# M1_Shield_Radio_V1_3_2.net
KiCad netlist of a schematic drawn in EAGLE
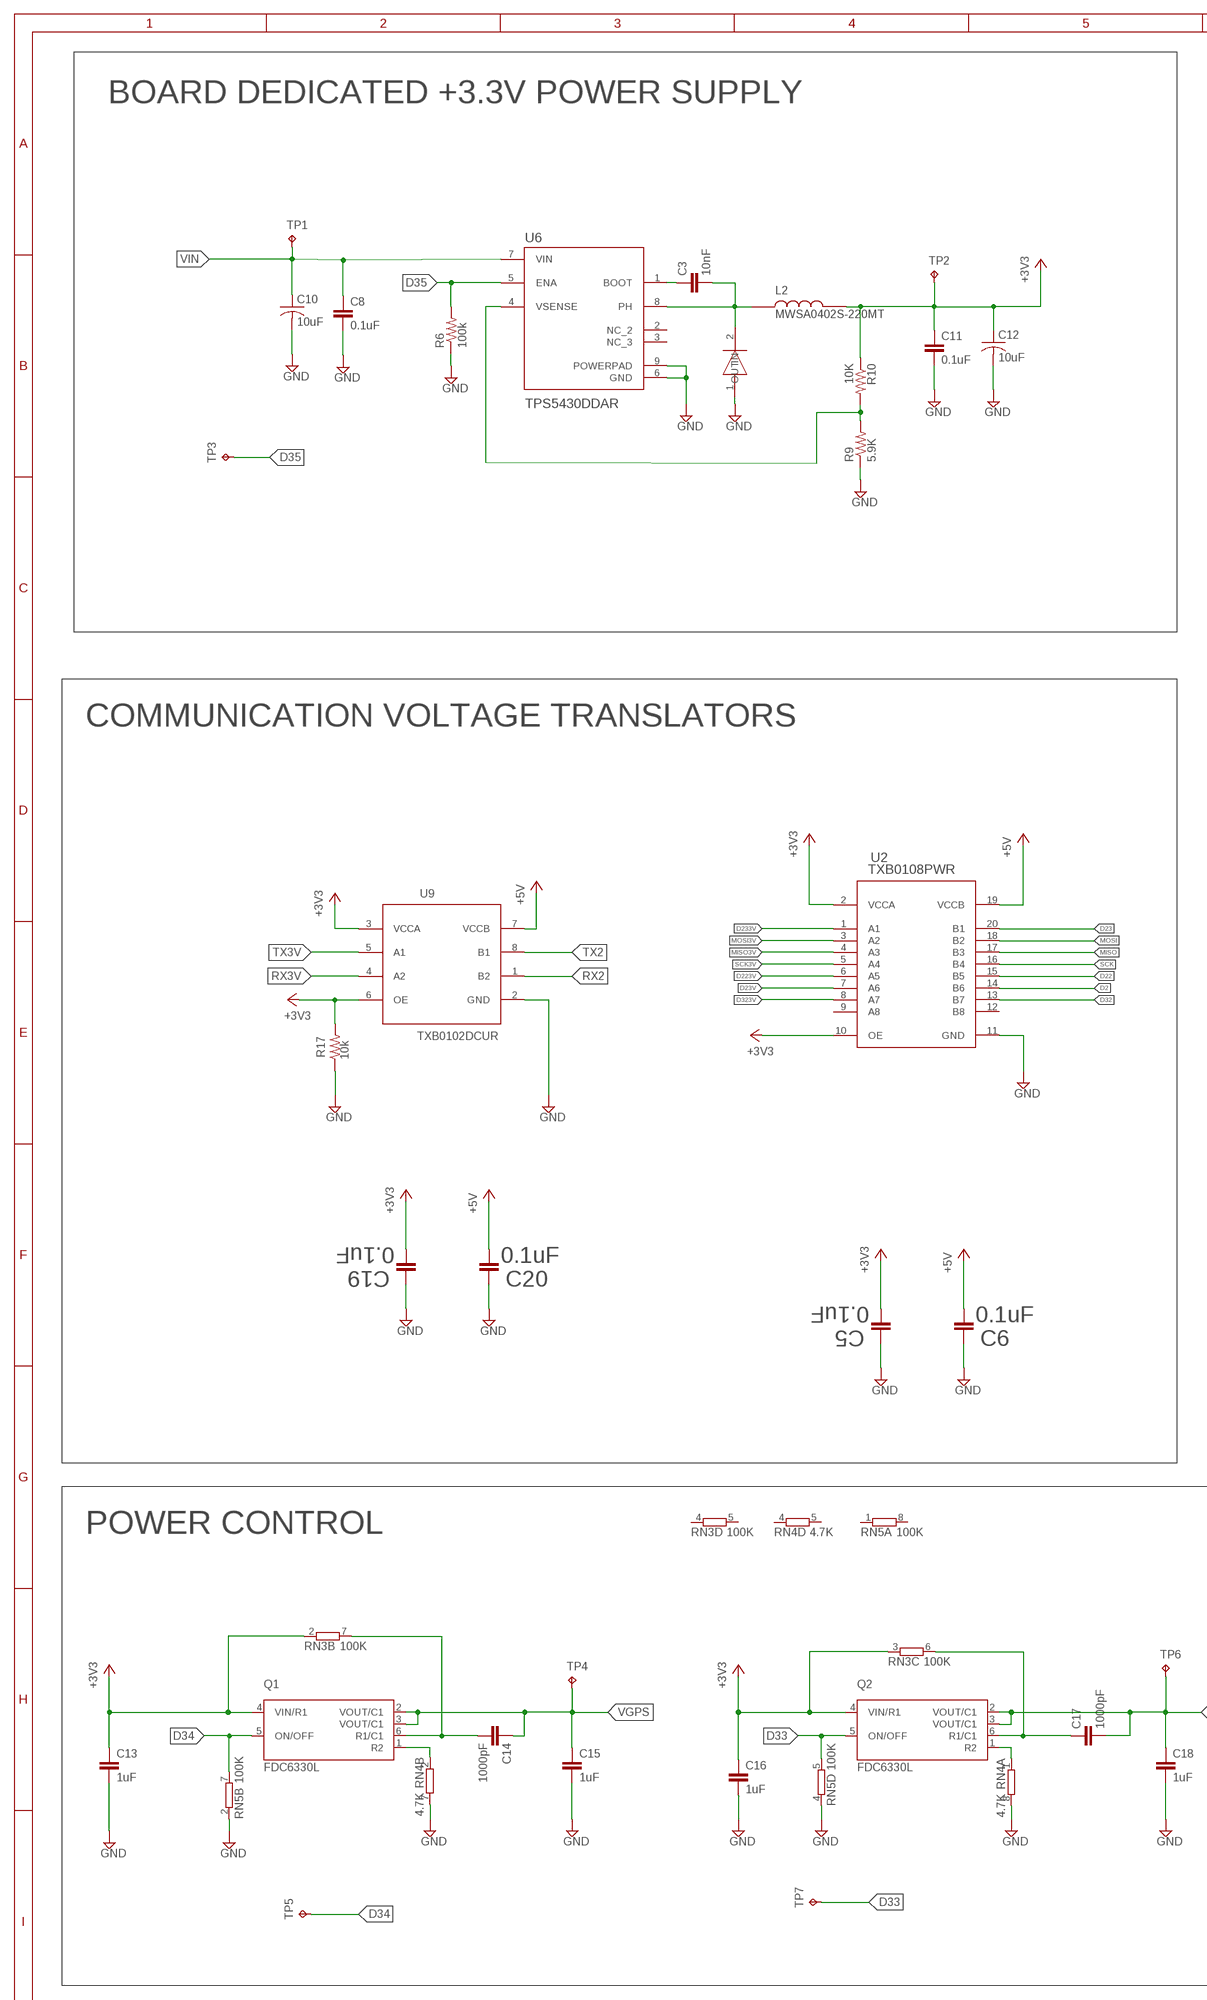
[diagram p0: schematic, sheet 1, part 1 of 2]
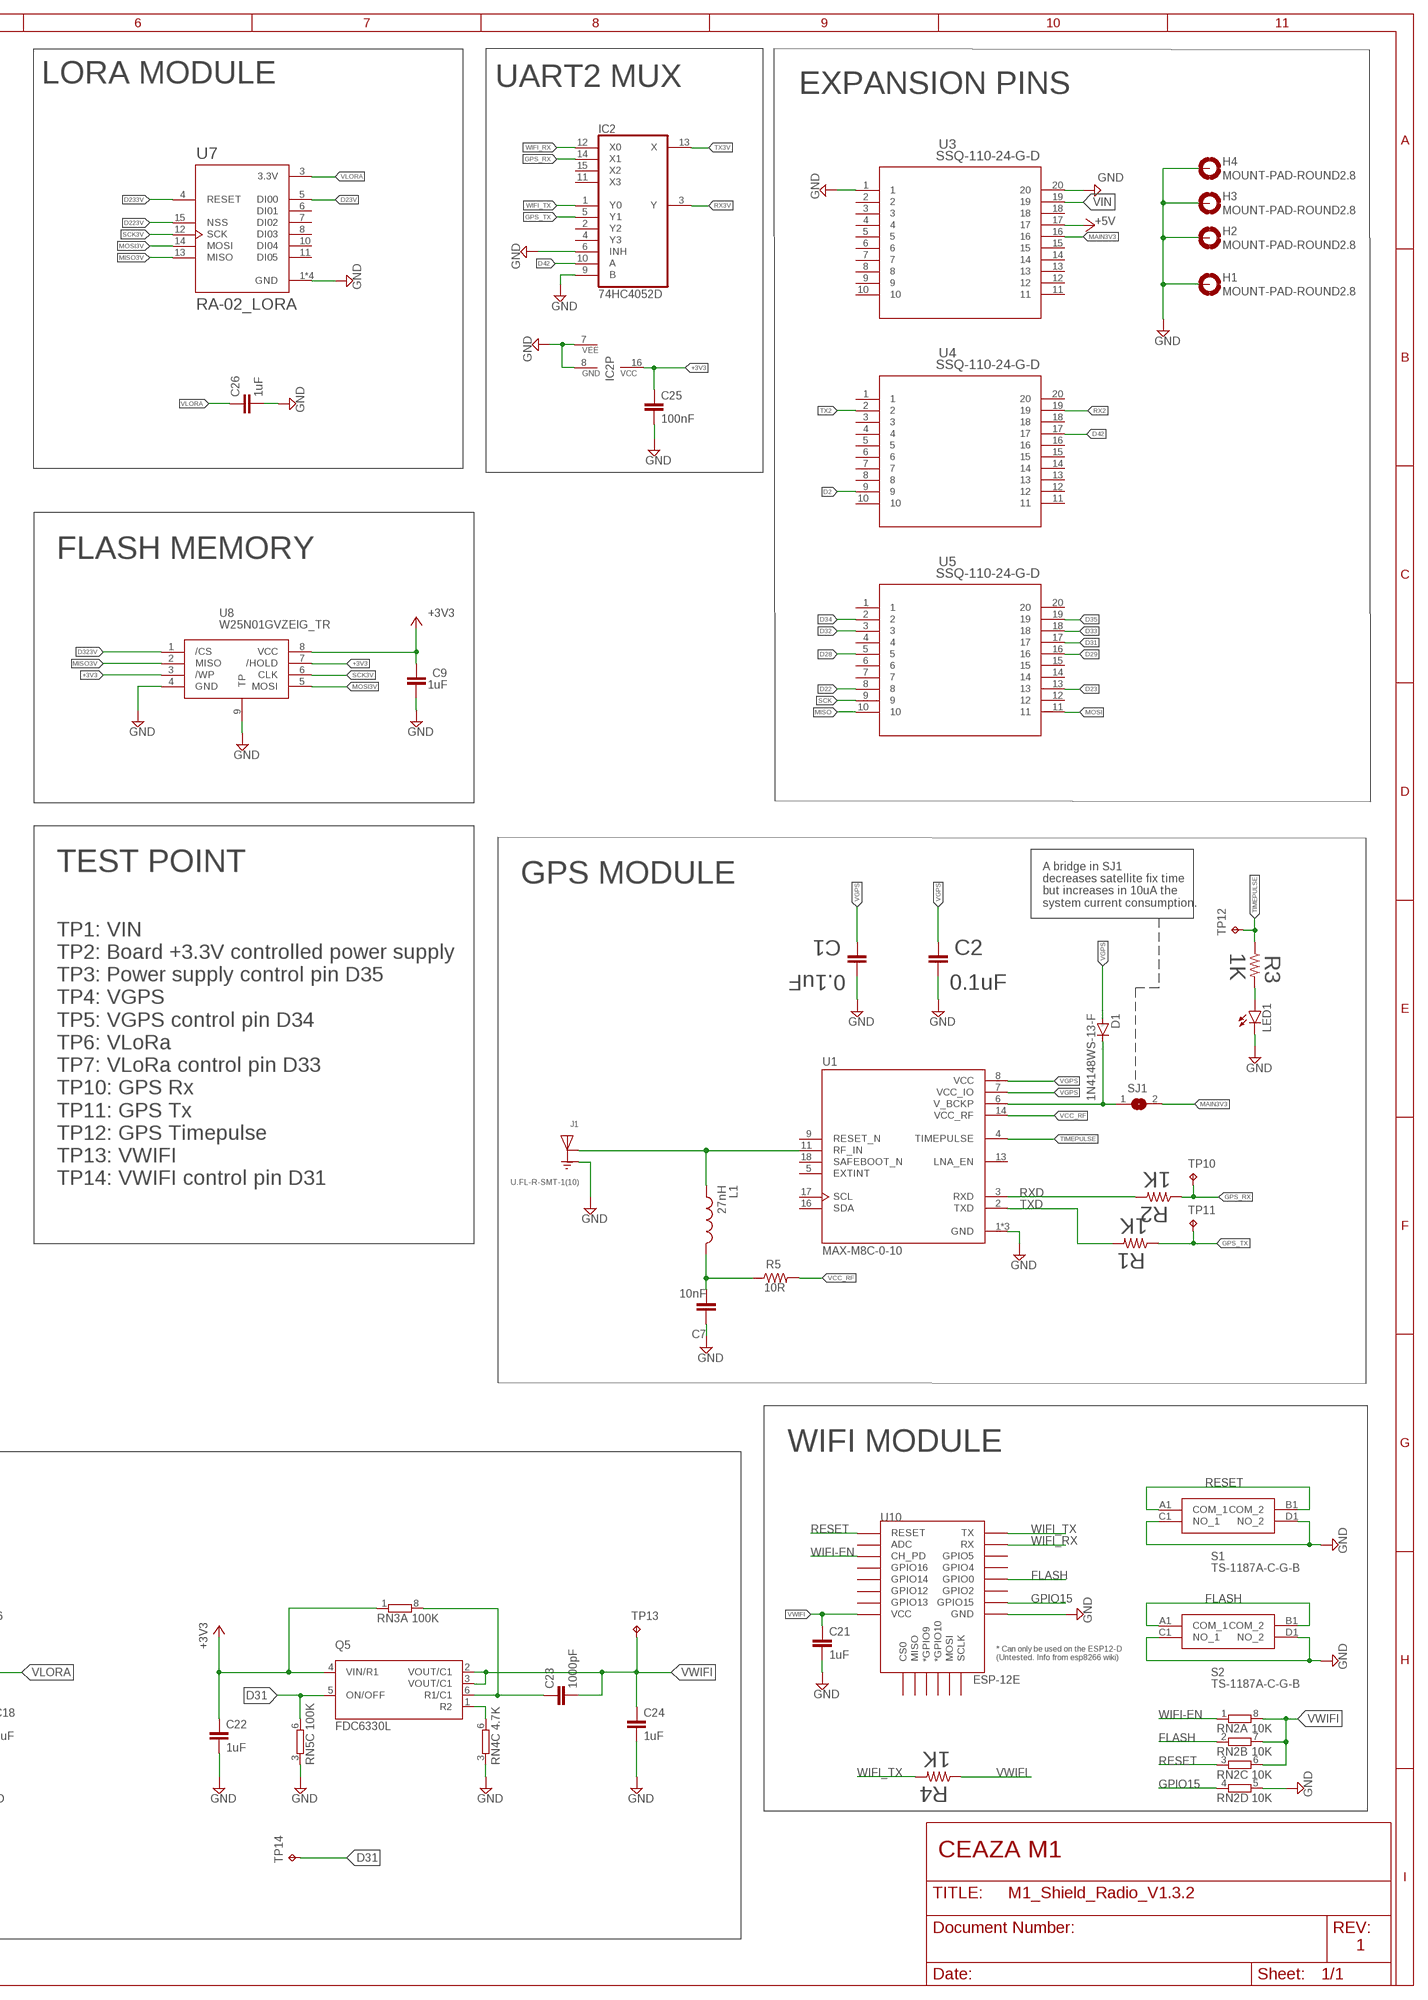
[diagram p1: schematic, sheet 1, part 2 of 2]

(export (version "E")
  (design (tool "Eeschema 10.0.6"))
  (components
    (comp (ref "C1")
      (value "0.1uF")
      (footprint "eagle-import:C0603K")
      (libsource (lib "eagle-import") (part "C-EUC0603K"))
    )
    (comp (ref "C2")
      (value "0.1uF")
      (footprint "eagle-import:C0603K")
      (libsource (lib "eagle-import") (part "C-EUC0603K"))
    )
    (comp (ref "C3")
      (value "10nF")
      (footprint "eagle-import:C0603K")
      (libsource (lib "eagle-import") (part "C-EUC0603K"))
    )
    (comp (ref "C5")
      (value "0.1uF")
      (footprint "eagle-import:C0603K")
      (libsource (lib "eagle-import") (part "C-EUC0603K"))
    )
    (comp (ref "C6")
      (value "0.1uF")
      (footprint "eagle-import:C0603K")
      (libsource (lib "eagle-import") (part "C-EUC0603K"))
    )
    (comp (ref "C7")
      (value "10nF")
      (footprint "eagle-import:C0603K")
      (libsource (lib "eagle-import") (part "C-EUC0603K"))
    )
    (comp (ref "C8")
      (value "0.1uF")
      (footprint "eagle-import:C0603K")
      (libsource (lib "eagle-import") (part "C-EUC0603K"))
    )
    (comp (ref "C9")
      (value "1uF")
      (footprint "eagle-import:C0603K")
      (libsource (lib "eagle-import") (part "C-EUC0603K"))
    )
    (comp (ref "C10")
      (value "10uF")
      (footprint "eagle-import:C0603K")
      (libsource (lib "eagle-import") (part "C-USC0603K"))
    )
    (comp (ref "C11")
      (value "0.1uF")
      (footprint "eagle-import:C0603K")
      (libsource (lib "eagle-import") (part "C-EUC0603K"))
    )
    (comp (ref "C12")
      (value "10uF")
      (footprint "eagle-import:C0603K")
      (libsource (lib "eagle-import") (part "C-USC0603K"))
    )
    (comp (ref "C13")
      (value "1uF")
      (footprint "eagle-import:C0603K")
      (libsource (lib "eagle-import") (part "C-EUC0603K"))
    )
    (comp (ref "C14")
      (value "1000pF")
      (footprint "eagle-import:C0603K")
      (libsource (lib "eagle-import") (part "C-EUC0603K"))
    )
    (comp (ref "C15")
      (value "1uF")
      (footprint "eagle-import:C0603K")
      (libsource (lib "eagle-import") (part "C-EUC0603K"))
    )
    (comp (ref "C16")
      (value "1uF")
      (footprint "eagle-import:C0603K")
      (libsource (lib "eagle-import") (part "C-EUC0603K"))
    )
    (comp (ref "C17")
      (value "1000pF")
      (footprint "eagle-import:C0603K")
      (libsource (lib "eagle-import") (part "C-EUC0603K"))
    )
    (comp (ref "C18")
      (value "1uF")
      (footprint "eagle-import:C0603K")
      (libsource (lib "eagle-import") (part "C-EUC0603K"))
    )
    (comp (ref "C19")
      (value "0.1uF")
      (footprint "eagle-import:C0603K")
      (libsource (lib "eagle-import") (part "C-EUC0603K"))
    )
    (comp (ref "C20")
      (value "0.1uF")
      (footprint "eagle-import:C0603K")
      (libsource (lib "eagle-import") (part "C-EUC0603K"))
    )
    (comp (ref "C21")
      (value "1uF")
      (footprint "eagle-import:C0603K")
      (libsource (lib "eagle-import") (part "C-EUC0603K"))
    )
    (comp (ref "C22")
      (value "1uF")
      (footprint "eagle-import:C0603K")
      (libsource (lib "eagle-import") (part "C-EUC0603K"))
    )
    (comp (ref "C23")
      (value "1000pF")
      (footprint "eagle-import:C0603K")
      (libsource (lib "eagle-import") (part "C-EUC0603K"))
    )
    (comp (ref "C24")
      (value "1uF")
      (footprint "eagle-import:C0603K")
      (libsource (lib "eagle-import") (part "C-EUC0603K"))
    )
    (comp (ref "C25")
      (value "100nF")
      (footprint "eagle-import:C0603K")
      (libsource (lib "eagle-import") (part "C-EUC0603K"))
    )
    (comp (ref "C26")
      (value "1uF")
      (footprint "eagle-import:C0603K")
      (libsource (lib "eagle-import") (part "C-EUC0603K"))
    )
    (comp (ref "D1")
      (value "1N4148WS-13-F")
      (footprint "eagle-import:SOD323-W")
      (libsource (lib "eagle-import") (part "DIODE-SOD323-W"))
    )
    (comp (ref "H1")
      (value "MOUNT-PAD-ROUND2.8")
      (footprint "eagle-import:2,8-PAD")
      (libsource (lib "eagle-import") (part "MOUNT-PAD-ROUND2.8"))
    )
    (comp (ref "H2")
      (value "MOUNT-PAD-ROUND2.8")
      (footprint "eagle-import:2,8-PAD")
      (libsource (lib "eagle-import") (part "MOUNT-PAD-ROUND2.8"))
    )
    (comp (ref "H3")
      (value "MOUNT-PAD-ROUND2.8")
      (footprint "eagle-import:2,8-PAD")
      (libsource (lib "eagle-import") (part "MOUNT-PAD-ROUND2.8"))
    )
    (comp (ref "H4")
      (value "MOUNT-PAD-ROUND2.8")
      (footprint "eagle-import:2,8-PAD")
      (libsource (lib "eagle-import") (part "MOUNT-PAD-ROUND2.8"))
    )
    (comp (ref "IC2")
      (value "74HC4052D")
      (footprint "eagle-import:SO16")
      (libsource (lib "eagle-import") (part "4052D"))
    )
    (comp (ref "J1")
      (value "U.FL-R-SMT-1(10)")
      (footprint "eagle-import:HRS_U.FL-R-SMT-1(10)")
      (fields
        (field (name "DIGI-KEY_PART_NUMBER") "H11891CT-ND")
        (field (name "MF") "Hirose")
        (field (name "MP") "U.FL-R-SMT-1_10_")
      )
      (libsource (lib "eagle-import") (part "U.FL-R-SMT-1(10)"))
    )
    (comp (ref "L1")
      (value "27nH")
      (footprint "eagle-import:INDC1005X55N")
      (fields
        (field (name "DIGI-KEY_PART_NUMBER") "490-2628-1-ND")
        (field (name "MF") "Murata")
        (field (name "MP") "LQG15HS27NJ02D")
      )
      (libsource (lib "eagle-import") (part "LQG15HS27NJ02D"))
    )
    (comp (ref "L2")
      (value "MWSA0402S-220MT")
      (footprint "eagle-import:MWSA0402S-220MT")
      (libsource (lib "eagle-import") (part "MWSA0402S-220MT"))
    )
    (comp (ref "LED1")
      (value "LEDCHIP-LED0805")
      (footprint "eagle-import:CHIP-LED0805")
      (libsource (lib "eagle-import") (part "LEDCHIP-LED0805"))
    )
    (comp (ref "Q1")
      (value "FDC6330L")
      (footprint "eagle-import:SOT95P280X110-6N")
      (fields (field (name "DIGI-KEY_PART_NUMBER") "FDC6330LCT-ND") (field (name "MF") "ON Semiconductor"))
      (libsource (lib "eagle-import") (part "FDC6330L"))
    )
    (comp (ref "Q2")
      (value "FDC6330L")
      (footprint "eagle-import:SOT95P280X110-6N")
      (fields (field (name "DIGI-KEY_PART_NUMBER") "FDC6330LCT-ND") (field (name "MF") "ON Semiconductor"))
      (libsource (lib "eagle-import") (part "FDC6330L"))
    )
    (comp (ref "Q5")
      (value "FDC6330L")
      (footprint "eagle-import:SOT95P280X110-6N")
      (fields (field (name "DIGI-KEY_PART_NUMBER") "FDC6330LCT-ND") (field (name "MF") "ON Semiconductor"))
      (libsource (lib "eagle-import") (part "FDC6330L"))
    )
    (comp (ref "R1")
      (value "1K")
      (footprint "eagle-import:R0603")
      (libsource (lib "eagle-import") (part "R-US_R0603"))
    )
    (comp (ref "R2")
      (value "1K")
      (footprint "eagle-import:R0603")
      (libsource (lib "eagle-import") (part "R-US_R0603"))
    )
    (comp (ref "R3")
      (value "1K")
      (footprint "eagle-import:R0603")
      (libsource (lib "eagle-import") (part "R-US_R0603"))
    )
    (comp (ref "R4")
      (value "1K")
      (footprint "eagle-import:R0603")
      (libsource (lib "eagle-import") (part "R-US_R0603"))
    )
    (comp (ref "R5")
      (value "10R")
      (footprint "eagle-import:R0603")
      (libsource (lib "eagle-import") (part "R-US_R0603"))
    )
    (comp (ref "R6")
      (value "100k")
      (footprint "eagle-import:R0603")
      (libsource (lib "eagle-import") (part "R-US_R0603"))
    )
    (comp (ref "R9")
      (value "5.9K")
      (footprint "eagle-import:R0603")
      (libsource (lib "eagle-import") (part "R-US_R0603"))
    )
    (comp (ref "R10")
      (value "10K")
      (footprint "eagle-import:R0603")
      (libsource (lib "eagle-import") (part "R-US_R0603"))
    )
    (comp (ref "R17")
      (value "10k")
      (footprint "eagle-import:R0603")
      (libsource (lib "eagle-import") (part "R-US_R0603"))
    )
    (comp (ref "RN2")
      (value "10K")
      (footprint "eagle-import:0603-ARV")
      (libsource (lib "eagle-import") (part "4R-N0603-ARV"))
    )
    (comp (ref "RN3")
      (value "100K")
      (footprint "eagle-import:0603-ARV")
      (libsource (lib "eagle-import") (part "4R-N0603-ARV"))
    )
    (comp (ref "RN4")
      (value "4.7K")
      (footprint "eagle-import:0603-ARV")
      (libsource (lib "eagle-import") (part "4R-N0603-ARV"))
    )
    (comp (ref "RN5")
      (value "100K")
      (footprint "eagle-import:0603-ARV")
      (libsource (lib "eagle-import") (part "4R-N0603-ARV"))
    )
    (comp (ref "S1")
      (value "TS-1187A-C-G-B")
      (footprint "eagle-import:TS1187ACGB")
      (libsource (lib "eagle-import") (part "TS-1187A-C-G-B"))
    )
    (comp (ref "S2")
      (value "TS-1187A-C-G-B")
      (footprint "eagle-import:TS1187ACGB")
      (libsource (lib "eagle-import") (part "TS-1187A-C-G-B"))
    )
    (comp (ref "SJ1") (value "SJ") (footprint "eagle-import:SJ") (libsource (lib "eagle-import") (part "SJ")))
    (comp (ref "TP1")
      (value "TPB1,27")
      (footprint "eagle-import:B1,27")
      (libsource (lib "eagle-import") (part "TPB1,27"))
    )
    (comp (ref "TP2")
      (value "TPB1,27")
      (footprint "eagle-import:B1,27")
      (libsource (lib "eagle-import") (part "TPB1,27"))
    )
    (comp (ref "TP3")
      (value "TPB1,27")
      (footprint "eagle-import:B1,27")
      (libsource (lib "eagle-import") (part "TPB1,27"))
    )
    (comp (ref "TP4")
      (value "TPB1,27")
      (footprint "eagle-import:B1,27")
      (libsource (lib "eagle-import") (part "TPB1,27"))
    )
    (comp (ref "TP5")
      (value "TPB1,27")
      (footprint "eagle-import:B1,27")
      (libsource (lib "eagle-import") (part "TPB1,27"))
    )
    (comp (ref "TP6")
      (value "TPB1,27")
      (footprint "eagle-import:B1,27")
      (libsource (lib "eagle-import") (part "TPB1,27"))
    )
    (comp (ref "TP7")
      (value "TPB1,27")
      (footprint "eagle-import:B1,27")
      (libsource (lib "eagle-import") (part "TPB1,27"))
    )
    (comp (ref "TP10")
      (value "TPB1,27")
      (footprint "eagle-import:B1,27")
      (libsource (lib "eagle-import") (part "TPB1,27"))
    )
    (comp (ref "TP11")
      (value "TPB1,27")
      (footprint "eagle-import:B1,27")
      (libsource (lib "eagle-import") (part "TPB1,27"))
    )
    (comp (ref "TP12")
      (value "TPB1,27")
      (footprint "eagle-import:B1,27")
      (libsource (lib "eagle-import") (part "TPB1,27"))
    )
    (comp (ref "TP13")
      (value "TPB1,27")
      (footprint "eagle-import:B1,27")
      (libsource (lib "eagle-import") (part "TPB1,27"))
    )
    (comp (ref "TP14")
      (value "TPB1,27")
      (footprint "eagle-import:B1,27")
      (libsource (lib "eagle-import") (part "TPB1,27"))
    )
    (comp (ref "U$1")
      (value "SMA-SS34")
      (footprint "eagle-import:SMA-SS34")
      (libsource (lib "eagle-import") (part "SMA-SS34"))
    )
    (comp (ref "U1")
      (value "MAX-M8C-0-10")
      (footprint "eagle-import:XCVR_MAX-M8C-0-10")
      (fields (field (name "DIGI-KEY_PART_NUMBER") "672-1002-1-ND") (field (name "MF") "U-Blox America"))
      (libsource (lib "eagle-import") (part "MAX-M8C-0-10"))
    )
    (comp (ref "U2")
      (value "TXB0108PWR")
      (footprint "eagle-import:PW0020A_N")
      (fields (field (name "MANUFACTURER") "Texas Instruments"))
      (libsource (lib "eagle-import") (part "TXB0108PWR"))
    )
    (comp (ref "U3")
      (value "SSQ-110-24-G-D")
      (footprint "eagle-import:1-215307-0")
      (fields (field (name "MANUFACTURER_PART_NUMBER") "1-215307-0"))
      (libsource (lib "eagle-import") (part "1-215307-0"))
    )
    (comp (ref "U4")
      (value "SSQ-110-24-G-D")
      (footprint "eagle-import:1-215307-0")
      (fields (field (name "MANUFACTURER_PART_NUMBER") "1-215307-0"))
      (libsource (lib "eagle-import") (part "1-215307-0"))
    )
    (comp (ref "U5")
      (value "SSQ-110-24-G-D")
      (footprint "eagle-import:1-215307-0")
      (fields (field (name "MANUFACTURER_PART_NUMBER") "1-215307-0"))
      (libsource (lib "eagle-import") (part "1-215307-0"))
    )
    (comp (ref "U6")
      (value "TPS5430DDAR")
      (footprint "eagle-import:CONV_TPS5430DDAR")
      (fields (field (name "MF") "Texas Instruments"))
      (libsource (lib "eagle-import") (part "TPS5430DDAR"))
    )
    (comp (ref "U7")
      (value "RA-02_LORA")
      (footprint "eagle-import:MODULE_RA-02_LORA")
      (fields (field (name "MF") "AI-Thinker") (field (name "MP") "Ra-02 LoRa"))
      (libsource (lib "eagle-import") (part "RA-02_LORA"))
    )
    (comp (ref "U8")
      (value "W25N01GVZEIG_TR")
      (footprint "eagle-import:W25N01GVZEIGTR")
      (libsource (lib "eagle-import") (part "W25N01GVZEIG_TR"))
    )
    (comp (ref "U9")
      (value "TXB0102DCUR")
      (footprint "eagle-import:DCU0008A_L")
      (fields
        (field (name "ALTERNATE_PARTNUMBER") "TXB0102DCUT")
        (field (name "MANUFACTURER") "Texas Instruments")
      )
      (libsource (lib "eagle-import") (part "TXB0102DCURDCU0008A_L"))
    )
    (comp (ref "U10")
      (value "ESP-12E")
      (footprint "eagle-import:ESP12E-SMD")
      (libsource (lib "eagle-import") (part "ESP12ESMD"))
    )
  )
  (nets
    (net (code "1") (name "+3V3") (class "Default")
      (node (ref "C11") (pin "1") (pinfunction "1_1") (pintype "passive"))
      (node (ref "C12") (pin "1") (pinfunction "1_1") (pintype "passive"))
      (node (ref "C13") (pin "1") (pinfunction "1_1") (pintype "passive"))
      (node (ref "C16") (pin "1") (pinfunction "1_1") (pintype "passive"))
      (node (ref "C19") (pin "2") (pinfunction "2_2") (pintype "passive"))
      (node (ref "C22") (pin "1") (pinfunction "1_1") (pintype "passive"))
      (node (ref "C25") (pin "1") (pinfunction "1_1") (pintype "passive"))
      (node (ref "C5") (pin "2") (pinfunction "2_2") (pintype "passive"))
      (node (ref "C9") (pin "1") (pinfunction "1_1") (pintype "passive"))
      (node (ref "IC2") (pin "16") (pinfunction "VCC_16") (pintype "power_in"))
      (node (ref "L2") (pin "P$2") (pinfunction "P$2_P$2") (pintype "bidirectional"))
      (node (ref "Q1") (pin "4") (pinfunction "VIN/R1_4") (pintype "input"))
      (node (ref "Q2") (pin "4") (pinfunction "VIN/R1_4") (pintype "input"))
      (node (ref "Q5") (pin "4") (pinfunction "VIN/R1_4") (pintype "input"))
      (node (ref "R10") (pin "1") (pinfunction "1_1") (pintype "passive"))
      (node (ref "R17") (pin "2") (pinfunction "2_2") (pintype "passive"))
      (node (ref "RN3") (pin "1") (pinfunction "1_1") (pintype "passive"))
      (node (ref "RN3") (pin "2") (pinfunction "1_2") (pintype "passive"))
      (node (ref "RN3") (pin "3") (pinfunction "1_3") (pintype "passive"))
      (node (ref "TP2") (pin "TP") (pinfunction "TP_TP") (pintype "input"))
      (node (ref "U2") (pin "10") (pinfunction "OE_10") (pintype "input"))
      (node (ref "U2") (pin "2") (pinfunction "VCCA_2") (pintype "power_in"))
      (node (ref "U8") (pin "3") (pinfunction "/WP_3") (pintype "bidirectional"))
      (node (ref "U8") (pin "7") (pinfunction "/HOLD_7") (pintype "bidirectional"))
      (node (ref "U8") (pin "8") (pinfunction "VCC_8") (pintype "bidirectional"))
      (node (ref "U9") (pin "3") (pinfunction "VCCA_3") (pintype "power_in"))
      (node (ref "U9") (pin "6") (pinfunction "OE_6") (pintype "input"))
    )
    (net (code "2") (name "+5V") (class "Default")
      (node (ref "C20") (pin "2") (pinfunction "2_2") (pintype "passive"))
      (node (ref "C6") (pin "2") (pinfunction "2_2") (pintype "passive"))
      (node (ref "U2") (pin "19") (pinfunction "VCCB_19") (pintype "power_in"))
      (node (ref "U3") (pin "17") (pinfunction "17_17") (pintype "passive"))
      (node (ref "U9") (pin "7") (pinfunction "VCCB_7") (pintype "power_in"))
    )
    (net (code "3") (name "/FLASH") (class "Default")
      (node (ref "RN2") (pin "2") (pinfunction "1_2") (pintype "passive"))
      (node (ref "S2") (pin "A1") (pinfunction "COM_1_A1") (pintype "bidirectional"))
      (node (ref "S2") (pin "B1") (pinfunction "COM_2_B1") (pintype "bidirectional"))
      (node (ref "U10") (pin "GPIO0") (pinfunction "GPIO0_GPIO0") (pintype "bidirectional"))
    )
    (net (code "4") (name "/GPIO15") (class "Default")
      (node (ref "RN2") (pin "4") (pinfunction "1_4") (pintype "passive"))
      (node (ref "U10") (pin "GPIO15") (pinfunction "GPIO15_GPIO15") (pintype "bidirectional"))
    )
    (net (code "5") (name "/RESET") (class "Default")
      (node (ref "RN2") (pin "3") (pinfunction "1_3") (pintype "passive"))
      (node (ref "S1") (pin "A1") (pinfunction "COM_1_A1") (pintype "bidirectional"))
      (node (ref "S1") (pin "B1") (pinfunction "COM_2_B1") (pintype "bidirectional"))
      (node (ref "U10") (pin "RESET") (pinfunction "RESET_RESET") (pintype "bidirectional"))
    )
    (net (code "6") (name "/RXD") (class "Default")
      (node (ref "R2") (pin "2") (pinfunction "2_2") (pintype "passive"))
      (node (ref "U1") (pin "3") (pinfunction "RXD_3") (pintype "input"))
    )
    (net (code "7") (name "/TXD") (class "Default")
      (node (ref "R1") (pin "2") (pinfunction "2_2") (pintype "passive"))
      (node (ref "U1") (pin "2") (pinfunction "TXD_2") (pintype "output"))
    )
    (net (code "8") (name "/WIFI-EN") (class "Default")
      (node (ref "RN2") (pin "1") (pinfunction "1_1") (pintype "passive"))
      (node (ref "U10") (pin "CH_PD") (pinfunction "CH_PD_CH_PD") (pintype "bidirectional"))
    )
    (net (code "9") (name "D2") (class "Default")
      (node (ref "U2") (pin "14") (pinfunction "B6_14") (pintype "bidirectional"))
      (node (ref "U4") (pin "9") (pinfunction "9_9") (pintype "passive"))
    )
    (net (code "10") (name "D22") (class "Default")
      (node (ref "U2") (pin "15") (pinfunction "B5_15") (pintype "bidirectional"))
      (node (ref "U5") (pin "8") (pinfunction "8_8") (pintype "passive"))
    )
    (net (code "11") (name "D23") (class "Default")
      (node (ref "U2") (pin "20") (pinfunction "B1_20") (pintype "bidirectional"))
      (node (ref "U5") (pin "13") (pinfunction "13_13") (pintype "passive"))
    )
    (net (code "12") (name "D23V") (class "Default")
      (node (ref "U2") (pin "7") (pinfunction "A6_7") (pintype "bidirectional"))
      (node (ref "U7") (pin "5") (pinfunction "DI00_5") (pintype "bidirectional"))
    )
    (net (code "13") (name "D28") (class "Default")
      (node (ref "U5") (pin "5") (pinfunction "5_5") (pintype "passive"))
    )
    (net (code "14") (name "D29") (class "Default")
      (node (ref "U5") (pin "16") (pinfunction "16_16") (pintype "passive"))
    )
    (net (code "15") (name "D31") (class "Default")
      (node (ref "Q5") (pin "5") (pinfunction "ON/OFF_5") (pintype "input"))
      (node (ref "RN5") (pin "6") (pinfunction "2_6") (pintype "passive"))
      (node (ref "TP14") (pin "TP") (pinfunction "TP_TP") (pintype "input"))
      (node (ref "U5") (pin "17") (pinfunction "17_17") (pintype "passive"))
    )
    (net (code "16") (name "D32") (class "Default")
      (node (ref "U2") (pin "13") (pinfunction "B7_13") (pintype "bidirectional"))
      (node (ref "U5") (pin "3") (pinfunction "3_3") (pintype "passive"))
    )
    (net (code "17") (name "D33") (class "Default")
      (node (ref "Q2") (pin "5") (pinfunction "ON/OFF_5") (pintype "input"))
      (node (ref "RN5") (pin "5") (pinfunction "2_5") (pintype "passive"))
      (node (ref "TP7") (pin "TP") (pinfunction "TP_TP") (pintype "input"))
      (node (ref "U5") (pin "18") (pinfunction "18_18") (pintype "passive"))
    )
    (net (code "18") (name "D34") (class "Default")
      (node (ref "Q1") (pin "5") (pinfunction "ON/OFF_5") (pintype "input"))
      (node (ref "RN5") (pin "7") (pinfunction "2_7") (pintype "passive"))
      (node (ref "TP5") (pin "TP") (pinfunction "TP_TP") (pintype "input"))
      (node (ref "U5") (pin "2") (pinfunction "2_2") (pintype "passive"))
    )
    (net (code "19") (name "D35") (class "Default")
      (node (ref "R6") (pin "2") (pinfunction "2_2") (pintype "passive"))
      (node (ref "TP3") (pin "TP") (pinfunction "TP_TP") (pintype "input"))
      (node (ref "U5") (pin "19") (pinfunction "19_19") (pintype "passive"))
      (node (ref "U6") (pin "5") (pinfunction "ENA_5") (pintype "input"))
    )
    (net (code "20") (name "D42") (class "Default")
      (node (ref "IC2") (pin "10") (pinfunction "A_10") (pintype "input"))
      (node (ref "U4") (pin "17") (pinfunction "17_17") (pintype "passive"))
    )
    (net (code "21") (name "D223V") (class "Default")
      (node (ref "U2") (pin "6") (pinfunction "A5_6") (pintype "bidirectional"))
      (node (ref "U7") (pin "15") (pinfunction "NSS_15") (pintype "input"))
    )
    (net (code "22") (name "D233V") (class "Default")
      (node (ref "U2") (pin "1") (pinfunction "A1_1") (pintype "bidirectional"))
      (node (ref "U7") (pin "4") (pinfunction "RESET_4") (pintype "input"))
    )
    (net (code "23") (name "D323V") (class "Default")
      (node (ref "U2") (pin "8") (pinfunction "A7_8") (pintype "bidirectional"))
      (node (ref "U8") (pin "1") (pinfunction "/CS_1") (pintype "bidirectional"))
    )
    (net (code "24") (name "GND") (class "Default")
      (node (ref "C1") (pin "1") (pinfunction "1_1") (pintype "passive"))
      (node (ref "C10") (pin "2") (pinfunction "2_2") (pintype "passive"))
      (node (ref "C11") (pin "2") (pinfunction "2_2") (pintype "passive"))
      (node (ref "C12") (pin "2") (pinfunction "2_2") (pintype "passive"))
      (node (ref "C13") (pin "2") (pinfunction "2_2") (pintype "passive"))
      (node (ref "C15") (pin "2") (pinfunction "2_2") (pintype "passive"))
      (node (ref "C16") (pin "2") (pinfunction "2_2") (pintype "passive"))
      (node (ref "C18") (pin "2") (pinfunction "2_2") (pintype "passive"))
      (node (ref "C19") (pin "1") (pinfunction "1_1") (pintype "passive"))
      (node (ref "C2") (pin "1") (pinfunction "1_1") (pintype "passive"))
      (node (ref "C20") (pin "1") (pinfunction "1_1") (pintype "passive"))
      (node (ref "C21") (pin "2") (pinfunction "2_2") (pintype "passive"))
      (node (ref "C22") (pin "2") (pinfunction "2_2") (pintype "passive"))
      (node (ref "C24") (pin "2") (pinfunction "2_2") (pintype "passive"))
      (node (ref "C25") (pin "2") (pinfunction "2_2") (pintype "passive"))
      (node (ref "C26") (pin "2") (pinfunction "2_2") (pintype "passive"))
      (node (ref "C5") (pin "1") (pinfunction "1_1") (pintype "passive"))
      (node (ref "C6") (pin "1") (pinfunction "1_1") (pintype "passive"))
      (node (ref "C7") (pin "1") (pinfunction "1_1") (pintype "passive"))
      (node (ref "C8") (pin "2") (pinfunction "2_2") (pintype "passive"))
      (node (ref "C9") (pin "2") (pinfunction "2_2") (pintype "passive"))
      (node (ref "H1") (pin "B2,8") (pinfunction "MOUNT_B2,8") (pintype "passive"))
      (node (ref "H2") (pin "B2,8") (pinfunction "MOUNT_B2,8") (pintype "passive"))
      (node (ref "H3") (pin "B2,8") (pinfunction "MOUNT_B2,8") (pintype "passive"))
      (node (ref "H4") (pin "B2,8") (pinfunction "MOUNT_B2,8") (pintype "passive"))
      (node (ref "IC2") (pin "6") (pinfunction "INH_6") (pintype "input"))
      (node (ref "IC2") (pin "7") (pinfunction "VEE_7") (pintype "power_in"))
      (node (ref "IC2") (pin "8") (pinfunction "GND_8") (pintype "power_in"))
      (node (ref "IC2") (pin "9") (pinfunction "B_9") (pintype "input"))
      (node (ref "J1") (pin "1") (pinfunction "GND_1") (pintype "passive"))
      (node (ref "J1") (pin "3") (pinfunction "GND_3") (pintype "passive"))
      (node (ref "LED1") (pin "C") (pinfunction "C_C") (pintype "passive"))
      (node (ref "R17") (pin "1") (pinfunction "1_1") (pintype "passive"))
      (node (ref "R6") (pin "1") (pinfunction "1_1") (pintype "passive"))
      (node (ref "R9") (pin "1") (pinfunction "1_1") (pintype "passive"))
      (node (ref "RN2") (pin "5") (pinfunction "2_5") (pintype "passive"))
      (node (ref "RN4") (pin "3") (pinfunction "1_3") (pintype "passive"))
      (node (ref "RN4") (pin "7") (pinfunction "2_7") (pintype "passive"))
      (node (ref "RN4") (pin "8") (pinfunction "2_8") (pintype "passive"))
      (node (ref "RN5") (pin "2") (pinfunction "1_2") (pintype "passive"))
      (node (ref "RN5") (pin "3") (pinfunction "1_3") (pintype "passive"))
      (node (ref "RN5") (pin "4") (pinfunction "1_4") (pintype "passive"))
      (node (ref "S1") (pin "C1") (pinfunction "NO_1_C1") (pintype "bidirectional"))
      (node (ref "S1") (pin "D1") (pinfunction "NO_2_D1") (pintype "bidirectional"))
      (node (ref "S2") (pin "C1") (pinfunction "NO_1_C1") (pintype "bidirectional"))
      (node (ref "S2") (pin "D1") (pinfunction "NO_2_D1") (pintype "bidirectional"))
      (node (ref "U$1") (pin "1") (pinfunction "IN_1") (pintype "input"))
      (node (ref "U1") (pin "1") (pinfunction "GND_1") (pintype "power_in"))
      (node (ref "U1") (pin "10") (pinfunction "GND_10") (pintype "power_in"))
      (node (ref "U1") (pin "12") (pinfunction "GND_12") (pintype "power_in"))
      (node (ref "U10") (pin "GND") (pinfunction "GND_GND") (pintype "bidirectional"))
      (node (ref "U2") (pin "11") (pinfunction "GND_11") (pintype "power_in"))
      (node (ref "U3") (pin "1") (pinfunction "1_1") (pintype "passive"))
      (node (ref "U3") (pin "20") (pinfunction "20_20") (pintype "passive"))
      (node (ref "U6") (pin "6") (pinfunction "GND_6") (pintype "power_in"))
      (node (ref "U6") (pin "9") (pinfunction "POWERPAD_9") (pintype "power_in"))
      (node (ref "U7") (pin "1") (pinfunction "GND_1") (pintype "power_in"))
      (node (ref "U7") (pin "16") (pinfunction "GND_16") (pintype "power_in"))
      (node (ref "U7") (pin "2") (pinfunction "GND_2") (pintype "power_in"))
      (node (ref "U7") (pin "9") (pinfunction "GND_9") (pintype "power_in"))
      (node (ref "U8") (pin "4") (pinfunction "GND_4") (pintype "bidirectional"))
      (node (ref "U8") (pin "9") (pinfunction "TP_9") (pintype "bidirectional"))
      (node (ref "U9") (pin "2") (pinfunction "GND_2") (pintype "power_in"))
    )
    (net (code "25") (name "GPS_RX") (class "Default")
      (node (ref "IC2") (pin "14") (pinfunction "X1_14") (pintype "bidirectional"))
      (node (ref "R2") (pin "1") (pinfunction "1_1") (pintype "passive"))
      (node (ref "TP10") (pin "TP") (pinfunction "TP_TP") (pintype "input"))
    )
    (net (code "26") (name "GPS_TX") (class "Default")
      (node (ref "IC2") (pin "5") (pinfunction "Y1_5") (pintype "bidirectional"))
      (node (ref "R1") (pin "1") (pinfunction "1_1") (pintype "passive"))
      (node (ref "TP11") (pin "TP") (pinfunction "TP_TP") (pintype "input"))
    )
    (net (code "27") (name "MAIN3V3") (class "Default")
      (node (ref "SJ1") (pin "2") (pinfunction "2_2") (pintype "passive"))
      (node (ref "U3") (pin "16") (pinfunction "16_16") (pintype "passive"))
    )
    (net (code "28") (name "MISO") (class "Default")
      (node (ref "U2") (pin "17") (pinfunction "B3_17") (pintype "bidirectional"))
      (node (ref "U5") (pin "10") (pinfunction "10_10") (pintype "passive"))
    )
    (net (code "29") (name "MISO3V") (class "Default")
      (node (ref "U2") (pin "4") (pinfunction "A3_4") (pintype "bidirectional"))
      (node (ref "U7") (pin "13") (pinfunction "MISO_13") (pintype "output"))
      (node (ref "U8") (pin "2") (pinfunction "MISO_2") (pintype "bidirectional"))
    )
    (net (code "30") (name "MOSI") (class "Default")
      (node (ref "U2") (pin "18") (pinfunction "B2_18") (pintype "bidirectional"))
      (node (ref "U5") (pin "11") (pinfunction "11_11") (pintype "passive"))
    )
    (net (code "31") (name "MOSI3V") (class "Default")
      (node (ref "U2") (pin "3") (pinfunction "A2_3") (pintype "bidirectional"))
      (node (ref "U7") (pin "14") (pinfunction "MOSI_14") (pintype "input"))
      (node (ref "U8") (pin "5") (pinfunction "MOSI_5") (pintype "bidirectional"))
    )
    (net (code "32") (name "Net-(C7-Pad2)") (class "Default")
      (node (ref "C7") (pin "2") (pinfunction "2_2") (pintype "passive"))
      (node (ref "L1") (pin "2") (pinfunction "2_2") (pintype "passive"))
      (node (ref "R5") (pin "1") (pinfunction "1_1") (pintype "passive"))
    )
    (net (code "33") (name "Net-(J1-SIG)") (class "Default")
      (node (ref "J1") (pin "2") (pinfunction "SIG_2") (pintype "passive"))
      (node (ref "L1") (pin "1") (pinfunction "1_1") (pintype "passive"))
      (node (ref "U1") (pin "11") (pinfunction "RF_IN_11") (pintype "input"))
    )
    (net (code "34") (name "Net-(LED1-PadA)") (class "Default")
      (node (ref "LED1") (pin "A") (pinfunction "A_A") (pintype "passive"))
      (node (ref "R3") (pin "2") (pinfunction "2_2") (pintype "passive"))
    )
    (net (code "35") (name "Net-(Q1-R1{slash}C1)") (class "Default")
      (node (ref "C14") (pin "2") (pinfunction "2_2") (pintype "passive"))
      (node (ref "Q1") (pin "6") (pinfunction "R1/C1_6") (pintype "passive"))
      (node (ref "RN3") (pin "7") (pinfunction "2_7") (pintype "passive"))
    )
    (net (code "36") (name "Net-(Q1-R2)") (class "Default")
      (node (ref "Q1") (pin "1") (pinfunction "R2_1") (pintype "passive"))
      (node (ref "RN4") (pin "2") (pinfunction "1_2") (pintype "passive"))
    )
    (net (code "37") (name "Net-(Q2-R1{slash}C1)") (class "Default")
      (node (ref "C17") (pin "1") (pinfunction "1_1") (pintype "passive"))
      (node (ref "Q2") (pin "6") (pinfunction "R1/C1_6") (pintype "passive"))
      (node (ref "RN3") (pin "6") (pinfunction "2_6") (pintype "passive"))
    )
    (net (code "38") (name "Net-(Q2-R2)") (class "Default")
      (node (ref "Q2") (pin "1") (pinfunction "R2_1") (pintype "passive"))
      (node (ref "RN4") (pin "1") (pinfunction "1_1") (pintype "passive"))
    )
    (net (code "39") (name "Net-(Q5-R1{slash}C1)") (class "Default")
      (node (ref "C23") (pin "1") (pinfunction "1_1") (pintype "passive"))
      (node (ref "Q5") (pin "6") (pinfunction "R1/C1_6") (pintype "passive"))
      (node (ref "RN3") (pin "8") (pinfunction "2_8") (pintype "passive"))
    )
    (net (code "40") (name "Net-(Q5-R2)") (class "Default")
      (node (ref "Q5") (pin "1") (pinfunction "R2_1") (pintype "passive"))
      (node (ref "RN4") (pin "6") (pinfunction "2_6") (pintype "passive"))
    )
    (net (code "41") (name "Net-(U$1-OUT)") (class "Default")
      (node (ref "C3") (pin "2") (pinfunction "2_2") (pintype "passive"))
      (node (ref "L2") (pin "P$1") (pinfunction "P$1_P$1") (pintype "bidirectional"))
      (node (ref "U$1") (pin "2") (pinfunction "OUT_2") (pintype "bidirectional"))
      (node (ref "U6") (pin "8") (pinfunction "PH_8") (pintype "bidirectional"))
    )
    (net (code "42") (name "Net-(U1-V_BCKP)") (class "Default")
      (node (ref "D1") (pin "C") (pinfunction "C_C") (pintype "passive"))
      (node (ref "SJ1") (pin "1") (pinfunction "1_1") (pintype "passive"))
      (node (ref "U1") (pin "6") (pinfunction "V_BCKP_6") (pintype "power_in"))
    )
    (net (code "43") (name "Net-(U6-BOOT)") (class "Default")
      (node (ref "C3") (pin "1") (pinfunction "1_1") (pintype "passive"))
      (node (ref "U6") (pin "1") (pinfunction "BOOT_1") (pintype "output"))
    )
    (net (code "44") (name "Net-(U6-VSENSE)") (class "Default")
      (node (ref "R10") (pin "2") (pinfunction "2_2") (pintype "passive"))
      (node (ref "R9") (pin "2") (pinfunction "2_2") (pintype "passive"))
      (node (ref "U6") (pin "4") (pinfunction "VSENSE_4") (pintype "input"))
    )
    (net (code "45") (name "RX2") (class "Default")
      (node (ref "U4") (pin "19") (pinfunction "19_19") (pintype "passive"))
      (node (ref "U9") (pin "1") (pinfunction "B2_1") (pintype "bidirectional"))
    )
    (net (code "46") (name "RX3V") (class "Default")
      (node (ref "IC2") (pin "3") (pinfunction "Y_3") (pintype "bidirectional"))
      (node (ref "U9") (pin "4") (pinfunction "A2_4") (pintype "bidirectional"))
    )
    (net (code "47") (name "SCK") (class "Default")
      (node (ref "U2") (pin "16") (pinfunction "B4_16") (pintype "bidirectional"))
      (node (ref "U5") (pin "9") (pinfunction "9_9") (pintype "passive"))
    )
    (net (code "48") (name "SCK3V") (class "Default")
      (node (ref "U2") (pin "5") (pinfunction "A4_5") (pintype "bidirectional"))
      (node (ref "U7") (pin "12") (pinfunction "SCK_12") (pintype "input"))
      (node (ref "U8") (pin "6") (pinfunction "CLK_6") (pintype "bidirectional"))
    )
    (net (code "49") (name "TIMEPULSE") (class "Default")
      (node (ref "R3") (pin "1") (pinfunction "1_1") (pintype "passive"))
      (node (ref "TP12") (pin "TP") (pinfunction "TP_TP") (pintype "input"))
      (node (ref "U1") (pin "4") (pinfunction "TIMEPULSE_4") (pintype "output"))
    )
    (net (code "50") (name "TX2") (class "Default")
      (node (ref "U4") (pin "2") (pinfunction "2_2") (pintype "passive"))
      (node (ref "U9") (pin "8") (pinfunction "B1_8") (pintype "bidirectional"))
    )
    (net (code "51") (name "TX3V") (class "Default")
      (node (ref "IC2") (pin "13") (pinfunction "X_13") (pintype "bidirectional"))
      (node (ref "U9") (pin "5") (pinfunction "A1_5") (pintype "bidirectional"))
    )
    (net (code "52") (name "VCC_RF") (class "Default")
      (node (ref "R5") (pin "2") (pinfunction "2_2") (pintype "passive"))
      (node (ref "U1") (pin "14") (pinfunction "VCC_RF_14") (pintype "power_in"))
    )
    (net (code "53") (name "VGPS") (class "Default")
      (node (ref "C1") (pin "2") (pinfunction "2_2") (pintype "passive"))
      (node (ref "C14") (pin "1") (pinfunction "1_1") (pintype "passive"))
      (node (ref "C15") (pin "1") (pinfunction "1_1") (pintype "passive"))
      (node (ref "C2") (pin "2") (pinfunction "2_2") (pintype "passive"))
      (node (ref "D1") (pin "A") (pinfunction "A_A") (pintype "passive"))
      (node (ref "Q1") (pin "2") (pinfunction "VOUT/C1_2") (pintype "output"))
      (node (ref "Q1") (pin "3") (pinfunction "VOUT/C1_3") (pintype "output"))
      (node (ref "TP4") (pin "TP") (pinfunction "TP_TP") (pintype "input"))
      (node (ref "U1") (pin "7") (pinfunction "VCC_IO_7") (pintype "power_in"))
      (node (ref "U1") (pin "8") (pinfunction "VCC_8") (pintype "power_in"))
    )
    (net (code "54") (name "VIN") (class "Default")
      (node (ref "C10") (pin "1") (pinfunction "1_1") (pintype "passive"))
      (node (ref "C8") (pin "1") (pinfunction "1_1") (pintype "passive"))
      (node (ref "TP1") (pin "TP") (pinfunction "TP_TP") (pintype "input"))
      (node (ref "U3") (pin "19") (pinfunction "19_19") (pintype "passive"))
      (node (ref "U6") (pin "7") (pinfunction "VIN_7") (pintype "power_in"))
    )
    (net (code "55") (name "VLORA") (class "Default")
      (node (ref "C17") (pin "2") (pinfunction "2_2") (pintype "passive"))
      (node (ref "C18") (pin "1") (pinfunction "1_1") (pintype "passive"))
      (node (ref "C26") (pin "1") (pinfunction "1_1") (pintype "passive"))
      (node (ref "Q2") (pin "2") (pinfunction "VOUT/C1_2") (pintype "output"))
      (node (ref "Q2") (pin "3") (pinfunction "VOUT/C1_3") (pintype "output"))
      (node (ref "TP6") (pin "TP") (pinfunction "TP_TP") (pintype "input"))
      (node (ref "U7") (pin "3") (pinfunction "3.3V_3") (pintype "power_in"))
    )
    (net (code "56") (name "VWIFI") (class "Default")
      (node (ref "C21") (pin "1") (pinfunction "1_1") (pintype "passive"))
      (node (ref "C23") (pin "2") (pinfunction "2_2") (pintype "passive"))
      (node (ref "C24") (pin "1") (pinfunction "1_1") (pintype "passive"))
      (node (ref "Q5") (pin "2") (pinfunction "VOUT/C1_2") (pintype "output"))
      (node (ref "Q5") (pin "3") (pinfunction "VOUT/C1_3") (pintype "output"))
      (node (ref "R4") (pin "1") (pinfunction "1_1") (pintype "passive"))
      (node (ref "RN2") (pin "6") (pinfunction "2_6") (pintype "passive"))
      (node (ref "RN2") (pin "7") (pinfunction "2_7") (pintype "passive"))
      (node (ref "RN2") (pin "8") (pinfunction "2_8") (pintype "passive"))
      (node (ref "TP13") (pin "TP") (pinfunction "TP_TP") (pintype "input"))
      (node (ref "U10") (pin "VCC") (pinfunction "VCC_VCC") (pintype "bidirectional"))
    )
    (net (code "57") (name "WIFI_RX") (class "Default")
      (node (ref "IC2") (pin "12") (pinfunction "X0_12") (pintype "bidirectional"))
      (node (ref "U10") (pin "RXD0") (pinfunction "RX_RXD0") (pintype "bidirectional"))
    )
    (net (code "58") (name "WIFI_TX") (class "Default")
      (node (ref "IC2") (pin "1") (pinfunction "Y0_1") (pintype "bidirectional"))
      (node (ref "R4") (pin "2") (pinfunction "2_2") (pintype "passive"))
      (node (ref "U10") (pin "TXD0") (pinfunction "TX_TXD0") (pintype "bidirectional"))
    )
    (net (code "59") (name "unconnected-(IC2A-X2-Pad15)") (class "Default")
      (node (ref "IC2") (pin "15") (pinfunction "X2_15") (pintype "bidirectional"))
    )
    (net (code "60") (name "unconnected-(IC2A-X3-Pad11)") (class "Default")
      (node (ref "IC2") (pin "11") (pinfunction "X3_11") (pintype "bidirectional"))
    )
    (net (code "61") (name "unconnected-(IC2A-Y2-Pad2)") (class "Default")
      (node (ref "IC2") (pin "2") (pinfunction "Y2_2") (pintype "bidirectional"))
    )
    (net (code "62") (name "unconnected-(IC2A-Y3-Pad4)") (class "Default")
      (node (ref "IC2") (pin "4") (pinfunction "Y3_4") (pintype "bidirectional"))
    )
    (net (code "63") (name "unconnected-(RN3D-1-Pad4)") (class "Default")
      (node (ref "RN3") (pin "4") (pinfunction "1_4") (pintype "passive"))
    )
    (net (code "64") (name "unconnected-(RN3D-2-Pad5)") (class "Default")
      (node (ref "RN3") (pin "5") (pinfunction "2_5") (pintype "passive"))
    )
    (net (code "65") (name "unconnected-(RN4D-1-Pad4)") (class "Default")
      (node (ref "RN4") (pin "4") (pinfunction "1_4") (pintype "passive"))
    )
    (net (code "66") (name "unconnected-(RN4D-2-Pad5)") (class "Default")
      (node (ref "RN4") (pin "5") (pinfunction "2_5") (pintype "passive"))
    )
    (net (code "67") (name "unconnected-(RN5-Pad1)") (class "Default")
      (node (ref "RN5") (pin "1") (pinfunction "1_1") (pintype "passive"))
    )
    (net (code "68") (name "unconnected-(RN5A-2-Pad8)") (class "Default")
      (node (ref "RN5") (pin "8") (pinfunction "2_8") (pintype "passive"))
    )
    (net (code "69") (name "unconnected-(U1-EXTINT-Pad5)") (class "Default")
      (node (ref "U1") (pin "5") (pinfunction "EXTINT_5") (pintype "input"))
    )
    (net (code "70") (name "unconnected-(U1-LNA_EN-Pad13)") (class "Default")
      (node (ref "U1") (pin "13") (pinfunction "LNA_EN_13") (pintype "output"))
    )
    (net (code "71") (name "unconnected-(U1-RESET_N-Pad9)") (class "Default")
      (node (ref "U1") (pin "9") (pinfunction "RESET_N_9") (pintype "input"))
    )
    (net (code "72") (name "unconnected-(U1-SAFEBOOT_N-Pad18)") (class "Default")
      (node (ref "U1") (pin "18") (pinfunction "SAFEBOOT_N_18") (pintype "input"))
    )
    (net (code "73") (name "unconnected-(U1-SCL-Pad17)") (class "Default")
      (node (ref "U1") (pin "17") (pinfunction "SCL_17") (pintype "input"))
    )
    (net (code "74") (name "unconnected-(U1-SDA-Pad16)") (class "Default")
      (node (ref "U1") (pin "16") (pinfunction "SDA_16") (pintype "bidirectional"))
    )
    (net (code "75") (name "unconnected-(U2-A8-Pad9)") (class "Default")
      (node (ref "U2") (pin "9") (pinfunction "A8_9") (pintype "bidirectional"))
    )
    (net (code "76") (name "unconnected-(U2-B8-Pad12)") (class "Default")
      (node (ref "U2") (pin "12") (pinfunction "B8_12") (pintype "bidirectional"))
    )
    (net (code "77") (name "unconnected-(U3-Pad2)") (class "Default")
      (node (ref "U3") (pin "2") (pinfunction "2_2") (pintype "passive"))
    )
    (net (code "78") (name "unconnected-(U3-Pad3)") (class "Default")
      (node (ref "U3") (pin "3") (pinfunction "3_3") (pintype "passive"))
    )
    (net (code "79") (name "unconnected-(U3-Pad4)") (class "Default")
      (node (ref "U3") (pin "4") (pinfunction "4_4") (pintype "passive"))
    )
    (net (code "80") (name "unconnected-(U3-Pad5)") (class "Default")
      (node (ref "U3") (pin "5") (pinfunction "5_5") (pintype "passive"))
    )
    (net (code "81") (name "unconnected-(U3-Pad6)") (class "Default")
      (node (ref "U3") (pin "6") (pinfunction "6_6") (pintype "passive"))
    )
    (net (code "82") (name "unconnected-(U3-Pad7)") (class "Default")
      (node (ref "U3") (pin "7") (pinfunction "7_7") (pintype "passive"))
    )
    (net (code "83") (name "unconnected-(U3-Pad8)") (class "Default")
      (node (ref "U3") (pin "8") (pinfunction "8_8") (pintype "passive"))
    )
    (net (code "84") (name "unconnected-(U3-Pad9)") (class "Default")
      (node (ref "U3") (pin "9") (pinfunction "9_9") (pintype "passive"))
    )
    (net (code "85") (name "unconnected-(U3-Pad10)") (class "Default")
      (node (ref "U3") (pin "10") (pinfunction "10_10") (pintype "passive"))
    )
    (net (code "86") (name "unconnected-(U3-Pad11)") (class "Default")
      (node (ref "U3") (pin "11") (pinfunction "11_11") (pintype "passive"))
    )
    (net (code "87") (name "unconnected-(U3-Pad12)") (class "Default")
      (node (ref "U3") (pin "12") (pinfunction "12_12") (pintype "passive"))
    )
    (net (code "88") (name "unconnected-(U3-Pad13)") (class "Default")
      (node (ref "U3") (pin "13") (pinfunction "13_13") (pintype "passive"))
    )
    (net (code "89") (name "unconnected-(U3-Pad14)") (class "Default")
      (node (ref "U3") (pin "14") (pinfunction "14_14") (pintype "passive"))
    )
    (net (code "90") (name "unconnected-(U3-Pad15)") (class "Default")
      (node (ref "U3") (pin "15") (pinfunction "15_15") (pintype "passive"))
    )
    (net (code "91") (name "unconnected-(U3-Pad18)") (class "Default")
      (node (ref "U3") (pin "18") (pinfunction "18_18") (pintype "passive"))
    )
    (net (code "92") (name "unconnected-(U4-Pad1)") (class "Default")
      (node (ref "U4") (pin "1") (pinfunction "1_1") (pintype "passive"))
    )
    (net (code "93") (name "unconnected-(U4-Pad3)") (class "Default")
      (node (ref "U4") (pin "3") (pinfunction "3_3") (pintype "passive"))
    )
    (net (code "94") (name "unconnected-(U4-Pad4)") (class "Default")
      (node (ref "U4") (pin "4") (pinfunction "4_4") (pintype "passive"))
    )
    (net (code "95") (name "unconnected-(U4-Pad5)") (class "Default")
      (node (ref "U4") (pin "5") (pinfunction "5_5") (pintype "passive"))
    )
    (net (code "96") (name "unconnected-(U4-Pad6)") (class "Default")
      (node (ref "U4") (pin "6") (pinfunction "6_6") (pintype "passive"))
    )
    (net (code "97") (name "unconnected-(U4-Pad7)") (class "Default")
      (node (ref "U4") (pin "7") (pinfunction "7_7") (pintype "passive"))
    )
    (net (code "98") (name "unconnected-(U4-Pad8)") (class "Default")
      (node (ref "U4") (pin "8") (pinfunction "8_8") (pintype "passive"))
    )
    (net (code "99") (name "unconnected-(U4-Pad10)") (class "Default")
      (node (ref "U4") (pin "10") (pinfunction "10_10") (pintype "passive"))
    )
    (net (code "100") (name "unconnected-(U4-Pad11)") (class "Default")
      (node (ref "U4") (pin "11") (pinfunction "11_11") (pintype "passive"))
    )
    (net (code "101") (name "unconnected-(U4-Pad12)") (class "Default")
      (node (ref "U4") (pin "12") (pinfunction "12_12") (pintype "passive"))
    )
    (net (code "102") (name "unconnected-(U4-Pad13)") (class "Default")
      (node (ref "U4") (pin "13") (pinfunction "13_13") (pintype "passive"))
    )
    (net (code "103") (name "unconnected-(U4-Pad14)") (class "Default")
      (node (ref "U4") (pin "14") (pinfunction "14_14") (pintype "passive"))
    )
    (net (code "104") (name "unconnected-(U4-Pad15)") (class "Default")
      (node (ref "U4") (pin "15") (pinfunction "15_15") (pintype "passive"))
    )
    (net (code "105") (name "unconnected-(U4-Pad16)") (class "Default")
      (node (ref "U4") (pin "16") (pinfunction "16_16") (pintype "passive"))
    )
    (net (code "106") (name "unconnected-(U4-Pad18)") (class "Default")
      (node (ref "U4") (pin "18") (pinfunction "18_18") (pintype "passive"))
    )
    (net (code "107") (name "unconnected-(U4-Pad20)") (class "Default")
      (node (ref "U4") (pin "20") (pinfunction "20_20") (pintype "passive"))
    )
    (net (code "108") (name "unconnected-(U5-Pad1)") (class "Default")
      (node (ref "U5") (pin "1") (pinfunction "1_1") (pintype "passive"))
    )
    (net (code "109") (name "unconnected-(U5-Pad4)") (class "Default")
      (node (ref "U5") (pin "4") (pinfunction "4_4") (pintype "passive"))
    )
    (net (code "110") (name "unconnected-(U5-Pad6)") (class "Default")
      (node (ref "U5") (pin "6") (pinfunction "6_6") (pintype "passive"))
    )
    (net (code "111") (name "unconnected-(U5-Pad7)") (class "Default")
      (node (ref "U5") (pin "7") (pinfunction "7_7") (pintype "passive"))
    )
    (net (code "112") (name "unconnected-(U5-Pad12)") (class "Default")
      (node (ref "U5") (pin "12") (pinfunction "12_12") (pintype "passive"))
    )
    (net (code "113") (name "unconnected-(U5-Pad14)") (class "Default")
      (node (ref "U5") (pin "14") (pinfunction "14_14") (pintype "passive"))
    )
    (net (code "114") (name "unconnected-(U5-Pad15)") (class "Default")
      (node (ref "U5") (pin "15") (pinfunction "15_15") (pintype "passive"))
    )
    (net (code "115") (name "unconnected-(U5-Pad20)") (class "Default")
      (node (ref "U5") (pin "20") (pinfunction "20_20") (pintype "passive"))
    )
    (net (code "116") (name "unconnected-(U6-NC_2-Pad2)") (class "Default")
      (node (ref "U6") (pin "2") (pinfunction "NC_2_2") (pintype "no_connect"))
    )
    (net (code "117") (name "unconnected-(U6-NC_3-Pad3)") (class "Default")
      (node (ref "U6") (pin "3") (pinfunction "NC_3_3") (pintype "no_connect"))
    )
    (net (code "118") (name "unconnected-(U7-DI01-Pad6)") (class "Default")
      (node (ref "U7") (pin "6") (pinfunction "DI01_6") (pintype "bidirectional"))
    )
    (net (code "119") (name "unconnected-(U7-DI02-Pad7)") (class "Default")
      (node (ref "U7") (pin "7") (pinfunction "DI02_7") (pintype "bidirectional"))
    )
    (net (code "120") (name "unconnected-(U7-DI03-Pad8)") (class "Default")
      (node (ref "U7") (pin "8") (pinfunction "DI03_8") (pintype "bidirectional"))
    )
    (net (code "121") (name "unconnected-(U7-DI04-Pad10)") (class "Default")
      (node (ref "U7") (pin "10") (pinfunction "DI04_10") (pintype "bidirectional"))
    )
    (net (code "122") (name "unconnected-(U7-DI05-Pad11)") (class "Default")
      (node (ref "U7") (pin "11") (pinfunction "DI05_11") (pintype "bidirectional"))
    )
    (net (code "123") (name "unconnected-(U10-*GPIO9-PadGPIO9)") (class "Default")
      (node (ref "U10") (pin "GPIO9") (pinfunction "*GPIO9_GPIO9") (pintype "bidirectional"))
    )
    (net (code "124") (name "unconnected-(U10-*GPIO10-PadGPIO10)") (class "Default")
      (node (ref "U10") (pin "GPIO10") (pinfunction "*GPIO10_GPIO10") (pintype "bidirectional"))
    )
    (net (code "125") (name "unconnected-(U10-PadADC)") (class "Default")
      (node (ref "U10") (pin "ADC") (pinfunction "ADC_ADC") (pintype "bidirectional"))
    )
    (net (code "126") (name "unconnected-(U10-PadCS0)") (class "Default")
      (node (ref "U10") (pin "CS0") (pinfunction "CS0_CS0") (pintype "bidirectional"))
    )
    (net (code "127") (name "unconnected-(U10-PadGPIO2)") (class "Default")
      (node (ref "U10") (pin "GPIO2") (pinfunction "GPIO2_GPIO2") (pintype "bidirectional"))
    )
    (net (code "128") (name "unconnected-(U10-PadGPIO4)") (class "Default")
      (node (ref "U10") (pin "GPIO4") (pinfunction "GPIO4_GPIO4") (pintype "bidirectional"))
    )
    (net (code "129") (name "unconnected-(U10-PadGPIO5)") (class "Default")
      (node (ref "U10") (pin "GPIO5") (pinfunction "GPIO5_GPIO5") (pintype "bidirectional"))
    )
    (net (code "130") (name "unconnected-(U10-PadGPIO12)") (class "Default")
      (node (ref "U10") (pin "GPIO12") (pinfunction "GPIO12_GPIO12") (pintype "bidirectional"))
    )
    (net (code "131") (name "unconnected-(U10-PadGPIO13)") (class "Default")
      (node (ref "U10") (pin "GPIO13") (pinfunction "GPIO13_GPIO13") (pintype "bidirectional"))
    )
    (net (code "132") (name "unconnected-(U10-PadGPIO14)") (class "Default")
      (node (ref "U10") (pin "GPIO14") (pinfunction "GPIO14_GPIO14") (pintype "bidirectional"))
    )
    (net (code "133") (name "unconnected-(U10-PadGPIO16)") (class "Default")
      (node (ref "U10") (pin "GPIO16") (pinfunction "GPIO16_GPIO16") (pintype "bidirectional"))
    )
    (net (code "134") (name "unconnected-(U10-PadMISO)") (class "Default")
      (node (ref "U10") (pin "MISO") (pinfunction "MISO_MISO") (pintype "bidirectional"))
    )
    (net (code "135") (name "unconnected-(U10-PadMOSI)") (class "Default")
      (node (ref "U10") (pin "MOSI") (pinfunction "MOSI_MOSI") (pintype "bidirectional"))
    )
    (net (code "136") (name "unconnected-(U10-PadSCLK)") (class "Default")
      (node (ref "U10") (pin "SCLK") (pinfunction "SCLK_SCLK") (pintype "bidirectional"))
    )
  )
)
